# projetEagleElecGroupeD.net
KiCad netlist of a schematic drawn in EAGLE
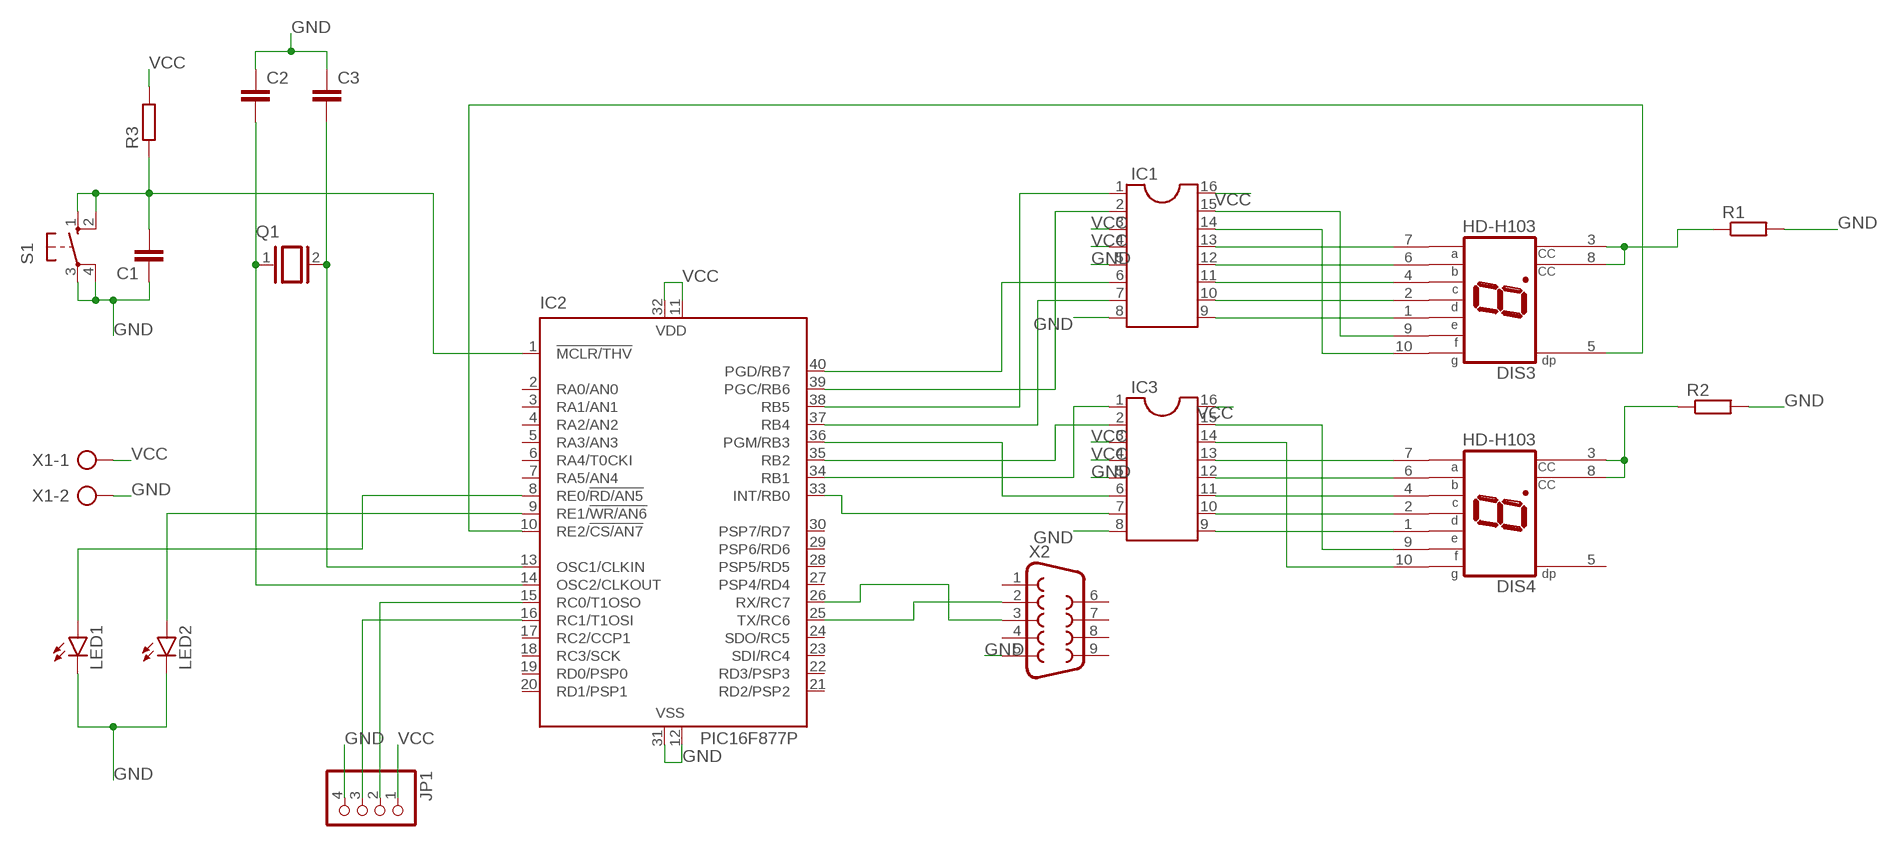
[diagram p0: schematic, sheet 1]

(export (version "E")
  (design (tool "Eeschema 10.0.6"))
  (components
    (comp (ref "C1")
      (value "C-EU025-025X050")
      (footprint "eagle-import:C025-025X050")
      (libsource (lib "eagle-import") (part "C-EU025-025X050"))
    )
    (comp (ref "C2")
      (value "C-EU025-025X050")
      (footprint "eagle-import:C025-025X050")
      (libsource (lib "eagle-import") (part "C-EU025-025X050"))
    )
    (comp (ref "C3")
      (value "C-EU025-025X050")
      (footprint "eagle-import:C025-025X050")
      (libsource (lib "eagle-import") (part "C-EU025-025X050"))
    )
    (comp (ref "DIS3")
      (value "HD-H103")
      (footprint "eagle-import:HDSP-M")
      (libsource (lib "eagle-import") (part "HD-H103"))
    )
    (comp (ref "DIS4")
      (value "HD-H103")
      (footprint "eagle-import:HDSP-M")
      (libsource (lib "eagle-import") (part "HD-H103"))
    )
    (comp (ref "IC1")
      (value "DIL16")
      (footprint "eagle-import:DIL16")
      (libsource (lib "eagle-import") (part "DIL16"))
    )
    (comp (ref "IC2")
      (value "PIC16F877P")
      (footprint "eagle-import:DIL40")
      (fields (field (name "MF") "MICROCHIP") (field (name "MPN") "PIC16F877-04/P"))
      (libsource (lib "eagle-import") (part "PIC16F87P7"))
    )
    (comp (ref "IC3")
      (value "DIL16")
      (footprint "eagle-import:DIL16")
      (libsource (lib "eagle-import") (part "DIL16"))
    )
    (comp (ref "JP1")
      (value "PINHD-1X4")
      (footprint "eagle-import:1X04")
      (libsource (lib "eagle-import") (part "PINHD-1X4"))
    )
    (comp (ref "LED1")
      (value "LED5MM")
      (footprint "eagle-import:LED5MM")
      (libsource (lib "eagle-import") (part "LED5MM"))
    )
    (comp (ref "LED2")
      (value "LED5MM")
      (footprint "eagle-import:LED5MM")
      (libsource (lib "eagle-import") (part "LED5MM"))
    )
    (comp (ref "Q1")
      (value "XTAL/S")
      (footprint "eagle-import:QS")
      (libsource (lib "eagle-import") (part "XTAL/S"))
    )
    (comp (ref "R1")
      (value "R-EU_0207/10")
      (footprint "eagle-import:0207_10")
      (libsource (lib "eagle-import") (part "R-EU_0207/10"))
    )
    (comp (ref "R2")
      (value "R-EU_0207/10")
      (footprint "eagle-import:0207_10")
      (libsource (lib "eagle-import") (part "R-EU_0207/10"))
    )
    (comp (ref "R3")
      (value "R-EU_0207/10")
      (footprint "eagle-import:0207_10")
      (libsource (lib "eagle-import") (part "R-EU_0207/10"))
    )
    (comp (ref "S1")
      (value "10-XX")
      (footprint "eagle-import:B3F-10XX")
      (fields (field (name "MPN") "B3F-1000"))
      (libsource (lib "eagle-import") (part "10-XX"))
    )
    (comp (ref "X1")
      (value "AK300/2")
      (footprint "eagle-import:AK300_2")
      (libsource (lib "eagle-import") (part "AK300/2"))
    )
    (comp (ref "X2")
      (value "F09H")
      (footprint "eagle-import:F09H")
      (libsource (lib "eagle-import") (part "F09H"))
    )
  )
  (nets
    (net (code "1") (name "/GND") (class "Default")
      (node (ref "C1") (pin "1") (pinfunction "1_1") (pintype "passive"))
      (node (ref "C2") (pin "1") (pinfunction "1_1") (pintype "passive"))
      (node (ref "C3") (pin "1") (pinfunction "1_1") (pintype "passive"))
      (node (ref "IC1") (pin "5") (pinfunction "5_5") (pintype "passive"))
      (node (ref "IC1") (pin "8") (pinfunction "8_8") (pintype "passive"))
      (node (ref "IC2") (pin "12") (pinfunction "VSS_12") (pintype "power_in"))
      (node (ref "IC2") (pin "31") (pinfunction "VSS_31") (pintype "power_in"))
      (node (ref "IC3") (pin "5") (pinfunction "5_5") (pintype "passive"))
      (node (ref "IC3") (pin "8") (pinfunction "8_8") (pintype "passive"))
      (node (ref "JP1") (pin "4") (pinfunction "4_4") (pintype "passive"))
      (node (ref "LED1") (pin "K") (pinfunction "C_K") (pintype "passive"))
      (node (ref "LED2") (pin "K") (pinfunction "C_K") (pintype "passive"))
      (node (ref "R1") (pin "2") (pinfunction "2_2") (pintype "passive"))
      (node (ref "R2") (pin "2") (pinfunction "2_2") (pintype "passive"))
      (node (ref "S1") (pin "3") (pinfunction "P_3") (pintype "passive"))
      (node (ref "S1") (pin "4") (pinfunction "P1_4") (pintype "passive"))
      (node (ref "X1") (pin "2") (pinfunction "KL_2") (pintype "passive"))
      (node (ref "X2") (pin "5") (pinfunction "5_5") (pintype "passive"))
    )
    (net (code "2") (name "/VCC") (class "Default")
      (node (ref "IC1") (pin "16") (pinfunction "16_16") (pintype "passive"))
      (node (ref "IC1") (pin "3") (pinfunction "3_3") (pintype "passive"))
      (node (ref "IC1") (pin "4") (pinfunction "4_4") (pintype "passive"))
      (node (ref "IC2") (pin "11") (pinfunction "VDD_11") (pintype "power_in"))
      (node (ref "IC2") (pin "32") (pinfunction "VDD_32") (pintype "power_in"))
      (node (ref "IC3") (pin "16") (pinfunction "16_16") (pintype "passive"))
      (node (ref "IC3") (pin "3") (pinfunction "3_3") (pintype "passive"))
      (node (ref "IC3") (pin "4") (pinfunction "4_4") (pintype "passive"))
      (node (ref "JP1") (pin "1") (pinfunction "1_1") (pintype "passive"))
      (node (ref "R3") (pin "2") (pinfunction "2_2") (pintype "passive"))
      (node (ref "X1") (pin "1") (pinfunction "KL_1") (pintype "passive"))
    )
    (net (code "3") (name "Net-(DIS3-A)") (class "Default")
      (node (ref "DIS3") (pin "7") (pinfunction "A_7") (pintype "passive"))
      (node (ref "IC1") (pin "13") (pinfunction "13_13") (pintype "passive"))
    )
    (net (code "4") (name "Net-(DIS3-B)") (class "Default")
      (node (ref "DIS3") (pin "6") (pinfunction "B_6") (pintype "passive"))
      (node (ref "IC1") (pin "12") (pinfunction "12_12") (pintype "passive"))
    )
    (net (code "5") (name "Net-(DIS3-C)") (class "Default")
      (node (ref "DIS3") (pin "4") (pinfunction "C_4") (pintype "passive"))
      (node (ref "IC1") (pin "11") (pinfunction "11_11") (pintype "passive"))
    )
    (net (code "6") (name "Net-(DIS3-CC-Pad3)") (class "Default")
      (node (ref "DIS3") (pin "3") (pinfunction "CC_3") (pintype "passive"))
      (node (ref "DIS3") (pin "8") (pinfunction "CC_8") (pintype "passive"))
      (node (ref "R1") (pin "1") (pinfunction "1_1") (pintype "passive"))
    )
    (net (code "7") (name "Net-(DIS3-D)") (class "Default")
      (node (ref "DIS3") (pin "2") (pinfunction "D_2") (pintype "passive"))
      (node (ref "IC1") (pin "10") (pinfunction "10_10") (pintype "passive"))
    )
    (net (code "8") (name "Net-(DIS3-DP)") (class "Default")
      (node (ref "DIS3") (pin "5") (pinfunction "DP_5") (pintype "passive"))
      (node (ref "IC2") (pin "10") (pinfunction "RE2/~{CS/AN7}_10") (pintype "bidirectional"))
    )
    (net (code "9") (name "Net-(DIS3-E)") (class "Default")
      (node (ref "DIS3") (pin "1") (pinfunction "E_1") (pintype "passive"))
      (node (ref "IC1") (pin "9") (pinfunction "9_9") (pintype "passive"))
    )
    (net (code "10") (name "Net-(DIS3-F)") (class "Default")
      (node (ref "DIS3") (pin "9") (pinfunction "F_9") (pintype "passive"))
      (node (ref "IC1") (pin "15") (pinfunction "15_15") (pintype "passive"))
    )
    (net (code "11") (name "Net-(DIS3-G)") (class "Default")
      (node (ref "DIS3") (pin "10") (pinfunction "G_10") (pintype "passive"))
      (node (ref "IC1") (pin "14") (pinfunction "14_14") (pintype "passive"))
    )
    (net (code "12") (name "Net-(DIS4-A)") (class "Default")
      (node (ref "DIS4") (pin "7") (pinfunction "A_7") (pintype "passive"))
      (node (ref "IC3") (pin "13") (pinfunction "13_13") (pintype "passive"))
    )
    (net (code "13") (name "Net-(DIS4-B)") (class "Default")
      (node (ref "DIS4") (pin "6") (pinfunction "B_6") (pintype "passive"))
      (node (ref "IC3") (pin "12") (pinfunction "12_12") (pintype "passive"))
    )
    (net (code "14") (name "Net-(DIS4-C)") (class "Default")
      (node (ref "DIS4") (pin "4") (pinfunction "C_4") (pintype "passive"))
      (node (ref "IC3") (pin "11") (pinfunction "11_11") (pintype "passive"))
    )
    (net (code "15") (name "Net-(DIS4-CC-Pad3)") (class "Default")
      (node (ref "DIS4") (pin "3") (pinfunction "CC_3") (pintype "passive"))
      (node (ref "DIS4") (pin "8") (pinfunction "CC_8") (pintype "passive"))
      (node (ref "R2") (pin "1") (pinfunction "1_1") (pintype "passive"))
    )
    (net (code "16") (name "Net-(DIS4-D)") (class "Default")
      (node (ref "DIS4") (pin "2") (pinfunction "D_2") (pintype "passive"))
      (node (ref "IC3") (pin "10") (pinfunction "10_10") (pintype "passive"))
    )
    (net (code "17") (name "Net-(DIS4-E)") (class "Default")
      (node (ref "DIS4") (pin "1") (pinfunction "E_1") (pintype "passive"))
      (node (ref "IC3") (pin "9") (pinfunction "9_9") (pintype "passive"))
    )
    (net (code "18") (name "Net-(DIS4-F)") (class "Default")
      (node (ref "DIS4") (pin "9") (pinfunction "F_9") (pintype "passive"))
      (node (ref "IC3") (pin "15") (pinfunction "15_15") (pintype "passive"))
    )
    (net (code "19") (name "Net-(DIS4-G)") (class "Default")
      (node (ref "DIS4") (pin "10") (pinfunction "G_10") (pintype "passive"))
      (node (ref "IC3") (pin "14") (pinfunction "14_14") (pintype "passive"))
    )
    (net (code "20") (name "Net-(IC2-INT{slash}RB0)") (class "Default")
      (node (ref "IC2") (pin "33") (pinfunction "INT/RB0_33") (pintype "bidirectional"))
      (node (ref "IC3") (pin "7") (pinfunction "7_7") (pintype "passive"))
    )
    (net (code "21") (name "Net-(IC2-OSC1{slash}CLKIN)") (class "Default")
      (node (ref "C3") (pin "2") (pinfunction "2_2") (pintype "passive"))
      (node (ref "IC2") (pin "13") (pinfunction "OSC1/CLKIN_13") (pintype "input"))
      (node (ref "Q1") (pin "2") (pinfunction "2_2") (pintype "passive"))
    )
    (net (code "22") (name "Net-(IC2-OSC2{slash}CLKOUT)") (class "Default")
      (node (ref "C2") (pin "2") (pinfunction "2_2") (pintype "passive"))
      (node (ref "IC2") (pin "14") (pinfunction "OSC2/CLKOUT_14") (pintype "output"))
      (node (ref "Q1") (pin "1") (pinfunction "1_1") (pintype "passive"))
    )
    (net (code "23") (name "Net-(IC2-PGC{slash}RB6)") (class "Default")
      (node (ref "IC1") (pin "2") (pinfunction "2_2") (pintype "passive"))
      (node (ref "IC2") (pin "39") (pinfunction "PGC/RB6_39") (pintype "bidirectional"))
    )
    (net (code "24") (name "Net-(IC2-PGD{slash}RB7)") (class "Default")
      (node (ref "IC1") (pin "6") (pinfunction "6_6") (pintype "passive"))
      (node (ref "IC2") (pin "40") (pinfunction "PGD/RB7_40") (pintype "bidirectional"))
    )
    (net (code "25") (name "Net-(IC2-PGM{slash}RB3)") (class "Default")
      (node (ref "IC2") (pin "36") (pinfunction "PGM/RB3_36") (pintype "bidirectional"))
      (node (ref "IC3") (pin "6") (pinfunction "6_6") (pintype "passive"))
    )
    (net (code "26") (name "Net-(IC2-RB1)") (class "Default")
      (node (ref "IC2") (pin "34") (pinfunction "RB1_34") (pintype "bidirectional"))
      (node (ref "IC3") (pin "1") (pinfunction "1_1") (pintype "passive"))
    )
    (net (code "27") (name "Net-(IC2-RB2)") (class "Default")
      (node (ref "IC2") (pin "35") (pinfunction "RB2_35") (pintype "bidirectional"))
      (node (ref "IC3") (pin "2") (pinfunction "2_2") (pintype "passive"))
    )
    (net (code "28") (name "Net-(IC2-RB4)") (class "Default")
      (node (ref "IC1") (pin "7") (pinfunction "7_7") (pintype "passive"))
      (node (ref "IC2") (pin "37") (pinfunction "RB4_37") (pintype "bidirectional"))
    )
    (net (code "29") (name "Net-(IC2-RB5)") (class "Default")
      (node (ref "IC1") (pin "1") (pinfunction "1_1") (pintype "passive"))
      (node (ref "IC2") (pin "38") (pinfunction "RB5_38") (pintype "bidirectional"))
    )
    (net (code "30") (name "Net-(IC2-RC0{slash}T1OSO)") (class "Default")
      (node (ref "IC2") (pin "15") (pinfunction "RC0/T1OSO_15") (pintype "bidirectional"))
      (node (ref "JP1") (pin "2") (pinfunction "2_2") (pintype "passive"))
    )
    (net (code "31") (name "Net-(IC2-RC1{slash}T1OSI)") (class "Default")
      (node (ref "IC2") (pin "16") (pinfunction "RC1/T1OSI_16") (pintype "bidirectional"))
      (node (ref "JP1") (pin "3") (pinfunction "3_3") (pintype "passive"))
    )
    (net (code "32") (name "Net-(IC2-RE0{slash}~{RD{slash}AN5})") (class "Default")
      (node (ref "IC2") (pin "8") (pinfunction "RE0/~{RD/AN5}_8") (pintype "bidirectional"))
      (node (ref "LED1") (pin "A") (pinfunction "A_A") (pintype "passive"))
    )
    (net (code "33") (name "Net-(IC2-RE1{slash}~{WR{slash}AN6})") (class "Default")
      (node (ref "IC2") (pin "9") (pinfunction "RE1/~{WR/AN6}_9") (pintype "bidirectional"))
      (node (ref "LED2") (pin "A") (pinfunction "A_A") (pintype "passive"))
    )
    (net (code "34") (name "Net-(IC2-RX{slash}RC7)") (class "Default")
      (node (ref "IC2") (pin "26") (pinfunction "RX/RC7_26") (pintype "bidirectional"))
      (node (ref "X2") (pin "3") (pinfunction "3_3") (pintype "passive"))
    )
    (net (code "35") (name "Net-(IC2-TX{slash}RC6)") (class "Default")
      (node (ref "IC2") (pin "25") (pinfunction "TX/RC6_25") (pintype "bidirectional"))
      (node (ref "X2") (pin "2") (pinfunction "2_2") (pintype "passive"))
    )
    (net (code "36") (name "Net-(IC2-~{MCLR{slash}THV})") (class "Default")
      (node (ref "C1") (pin "2") (pinfunction "2_2") (pintype "passive"))
      (node (ref "IC2") (pin "1") (pinfunction "~{MCLR/THV}_1") (pintype "input"))
      (node (ref "R3") (pin "1") (pinfunction "1_1") (pintype "passive"))
      (node (ref "S1") (pin "1") (pinfunction "S_1") (pintype "passive"))
      (node (ref "S1") (pin "2") (pinfunction "S1_2") (pintype "passive"))
    )
    (net (code "37") (name "unconnected-(DIS4-DP-Pad5)") (class "Default")
      (node (ref "DIS4") (pin "5") (pinfunction "DP_5") (pintype "passive"))
    )
    (net (code "38") (name "unconnected-(IC2-PSP4{slash}RD4-Pad27)") (class "Default")
      (node (ref "IC2") (pin "27") (pinfunction "PSP4/RD4_27") (pintype "bidirectional"))
    )
    (net (code "39") (name "unconnected-(IC2-PSP5{slash}RD5-Pad28)") (class "Default")
      (node (ref "IC2") (pin "28") (pinfunction "PSP5/RD5_28") (pintype "bidirectional"))
    )
    (net (code "40") (name "unconnected-(IC2-PSP6{slash}RD6-Pad29)") (class "Default")
      (node (ref "IC2") (pin "29") (pinfunction "PSP6/RD6_29") (pintype "bidirectional"))
    )
    (net (code "41") (name "unconnected-(IC2-PSP7{slash}RD7-Pad30)") (class "Default")
      (node (ref "IC2") (pin "30") (pinfunction "PSP7/RD7_30") (pintype "bidirectional"))
    )
    (net (code "42") (name "unconnected-(IC2-RA0{slash}AN0-Pad2)") (class "Default")
      (node (ref "IC2") (pin "2") (pinfunction "RA0/AN0_2") (pintype "bidirectional"))
    )
    (net (code "43") (name "unconnected-(IC2-RA1{slash}AN1-Pad3)") (class "Default")
      (node (ref "IC2") (pin "3") (pinfunction "RA1/AN1_3") (pintype "bidirectional"))
    )
    (net (code "44") (name "unconnected-(IC2-RA2{slash}AN2-Pad4)") (class "Default")
      (node (ref "IC2") (pin "4") (pinfunction "RA2/AN2_4") (pintype "bidirectional"))
    )
    (net (code "45") (name "unconnected-(IC2-RA3{slash}AN3-Pad5)") (class "Default")
      (node (ref "IC2") (pin "5") (pinfunction "RA3/AN3_5") (pintype "bidirectional"))
    )
    (net (code "46") (name "unconnected-(IC2-RA4{slash}T0CKI-Pad6)") (class "Default")
      (node (ref "IC2") (pin "6") (pinfunction "RA4/T0CKI_6") (pintype "bidirectional"))
    )
    (net (code "47") (name "unconnected-(IC2-RA5{slash}AN4-Pad7)") (class "Default")
      (node (ref "IC2") (pin "7") (pinfunction "RA5/AN4_7") (pintype "bidirectional"))
    )
    (net (code "48") (name "unconnected-(IC2-RC2{slash}CCP1-Pad17)") (class "Default")
      (node (ref "IC2") (pin "17") (pinfunction "RC2/CCP1_17") (pintype "bidirectional"))
    )
    (net (code "49") (name "unconnected-(IC2-RC3{slash}SCK-Pad18)") (class "Default")
      (node (ref "IC2") (pin "18") (pinfunction "RC3/SCK_18") (pintype "bidirectional"))
    )
    (net (code "50") (name "unconnected-(IC2-RD0{slash}PSP0-Pad19)") (class "Default")
      (node (ref "IC2") (pin "19") (pinfunction "RD0/PSP0_19") (pintype "bidirectional"))
    )
    (net (code "51") (name "unconnected-(IC2-RD1{slash}PSP1-Pad20)") (class "Default")
      (node (ref "IC2") (pin "20") (pinfunction "RD1/PSP1_20") (pintype "bidirectional"))
    )
    (net (code "52") (name "unconnected-(IC2-RD2{slash}PSP2-Pad21)") (class "Default")
      (node (ref "IC2") (pin "21") (pinfunction "RD2/PSP2_21") (pintype "bidirectional"))
    )
    (net (code "53") (name "unconnected-(IC2-RD3{slash}PSP3-Pad22)") (class "Default")
      (node (ref "IC2") (pin "22") (pinfunction "RD3/PSP3_22") (pintype "bidirectional"))
    )
    (net (code "54") (name "unconnected-(IC2-SDI{slash}RC4-Pad23)") (class "Default")
      (node (ref "IC2") (pin "23") (pinfunction "SDI/RC4_23") (pintype "bidirectional"))
    )
    (net (code "55") (name "unconnected-(IC2-SDO{slash}RC5-Pad24)") (class "Default")
      (node (ref "IC2") (pin "24") (pinfunction "SDO/RC5_24") (pintype "bidirectional"))
    )
    (net (code "56") (name "unconnected-(X2-Pad1)") (class "Default")
      (node (ref "X2") (pin "1") (pinfunction "1_1") (pintype "passive"))
    )
    (net (code "57") (name "unconnected-(X2-Pad4)") (class "Default")
      (node (ref "X2") (pin "4") (pinfunction "4_4") (pintype "passive"))
    )
    (net (code "58") (name "unconnected-(X2-Pad6)") (class "Default")
      (node (ref "X2") (pin "6") (pinfunction "6_6") (pintype "passive"))
    )
    (net (code "59") (name "unconnected-(X2-Pad7)") (class "Default")
      (node (ref "X2") (pin "7") (pinfunction "7_7") (pintype "passive"))
    )
    (net (code "60") (name "unconnected-(X2-Pad8)") (class "Default")
      (node (ref "X2") (pin "8") (pinfunction "8_8") (pintype "passive"))
    )
    (net (code "61") (name "unconnected-(X2-Pad9)") (class "Default")
      (node (ref "X2") (pin "9") (pinfunction "9_9") (pintype "passive"))
    )
  )
)
